# M837-pld-x.net
KiCad netlist of a schematic drawn in EAGLE
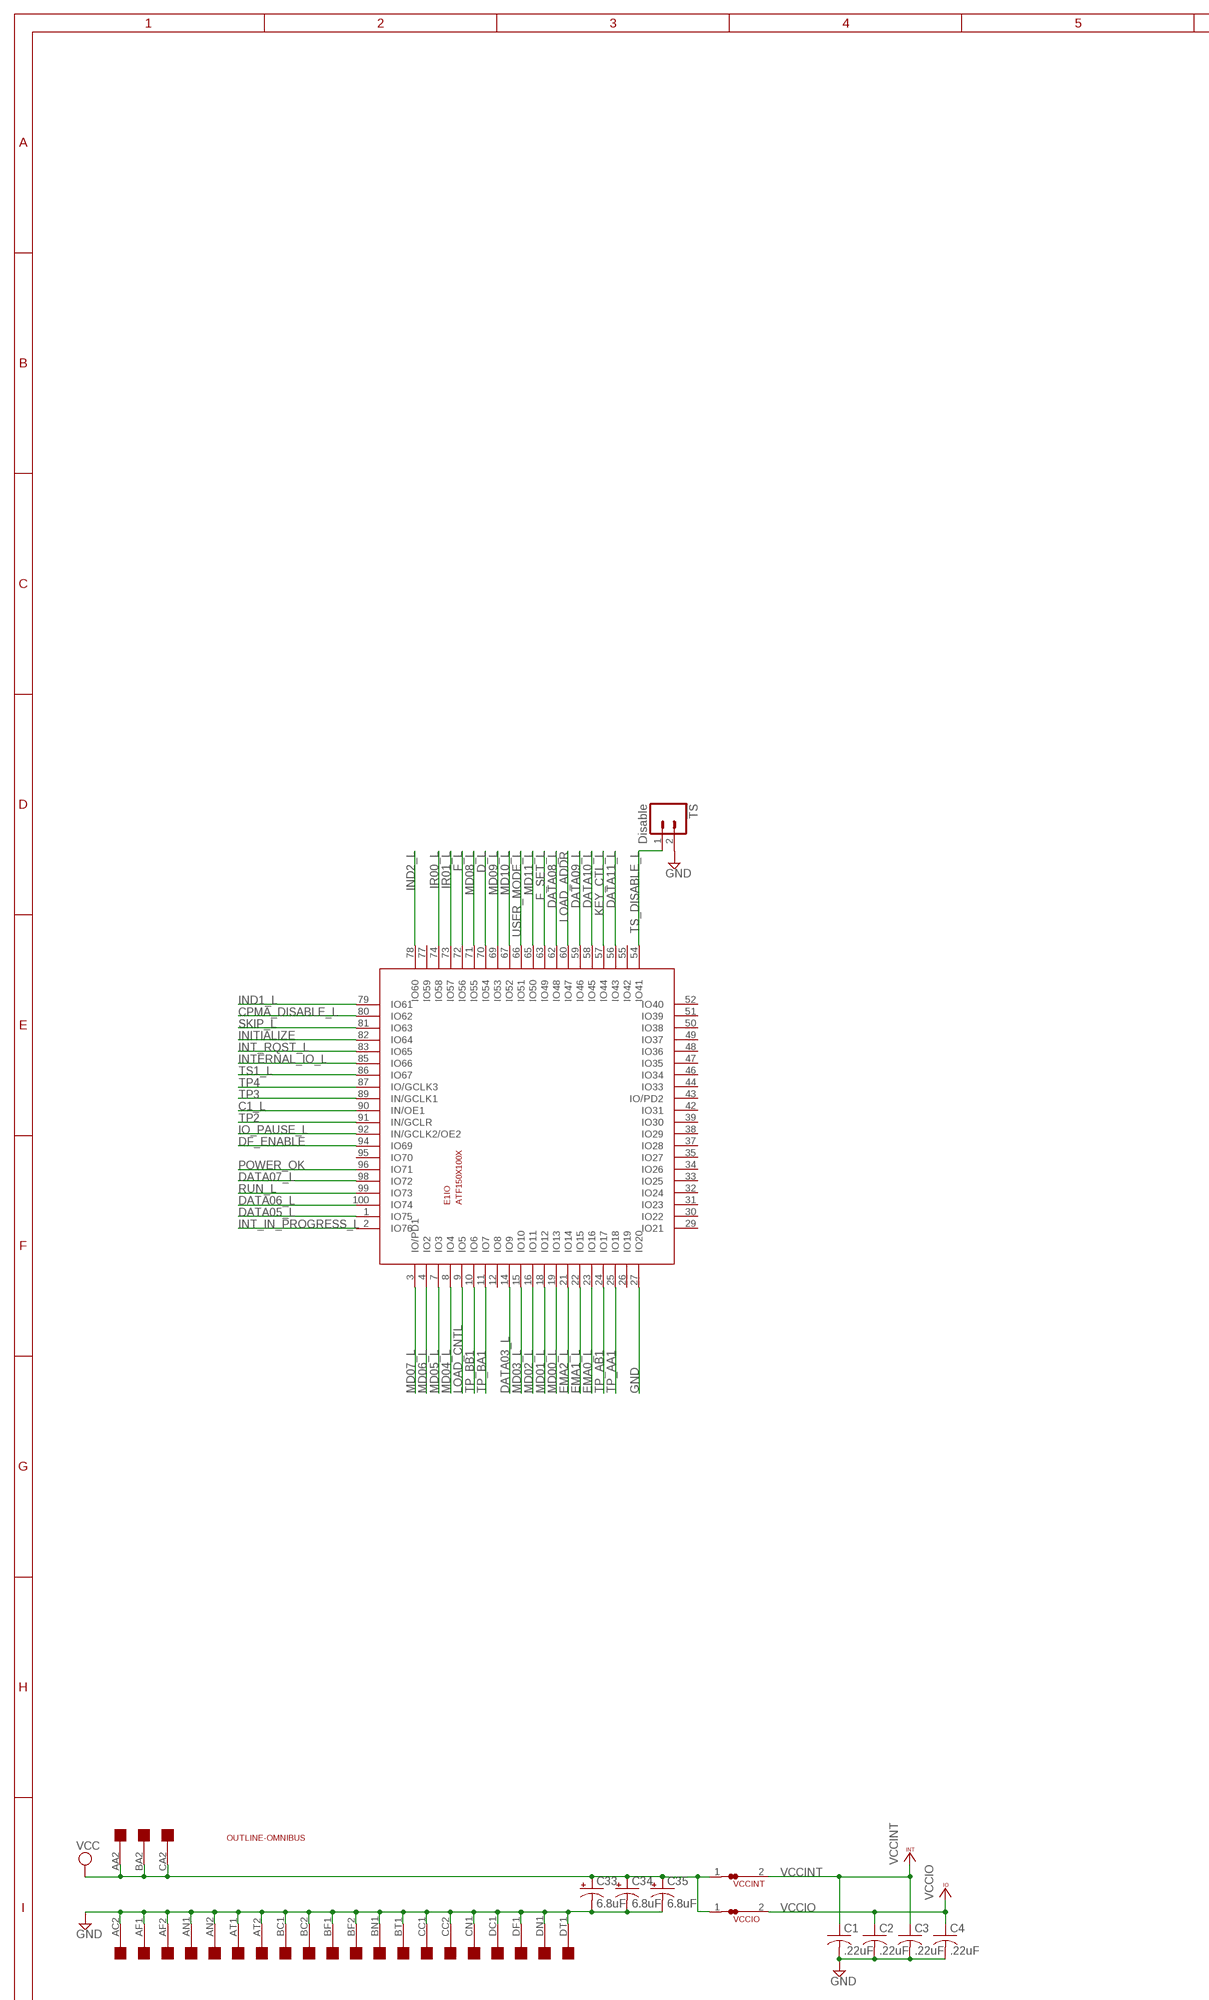
[diagram p0: schematic, sheet 1, part 1 of 2]
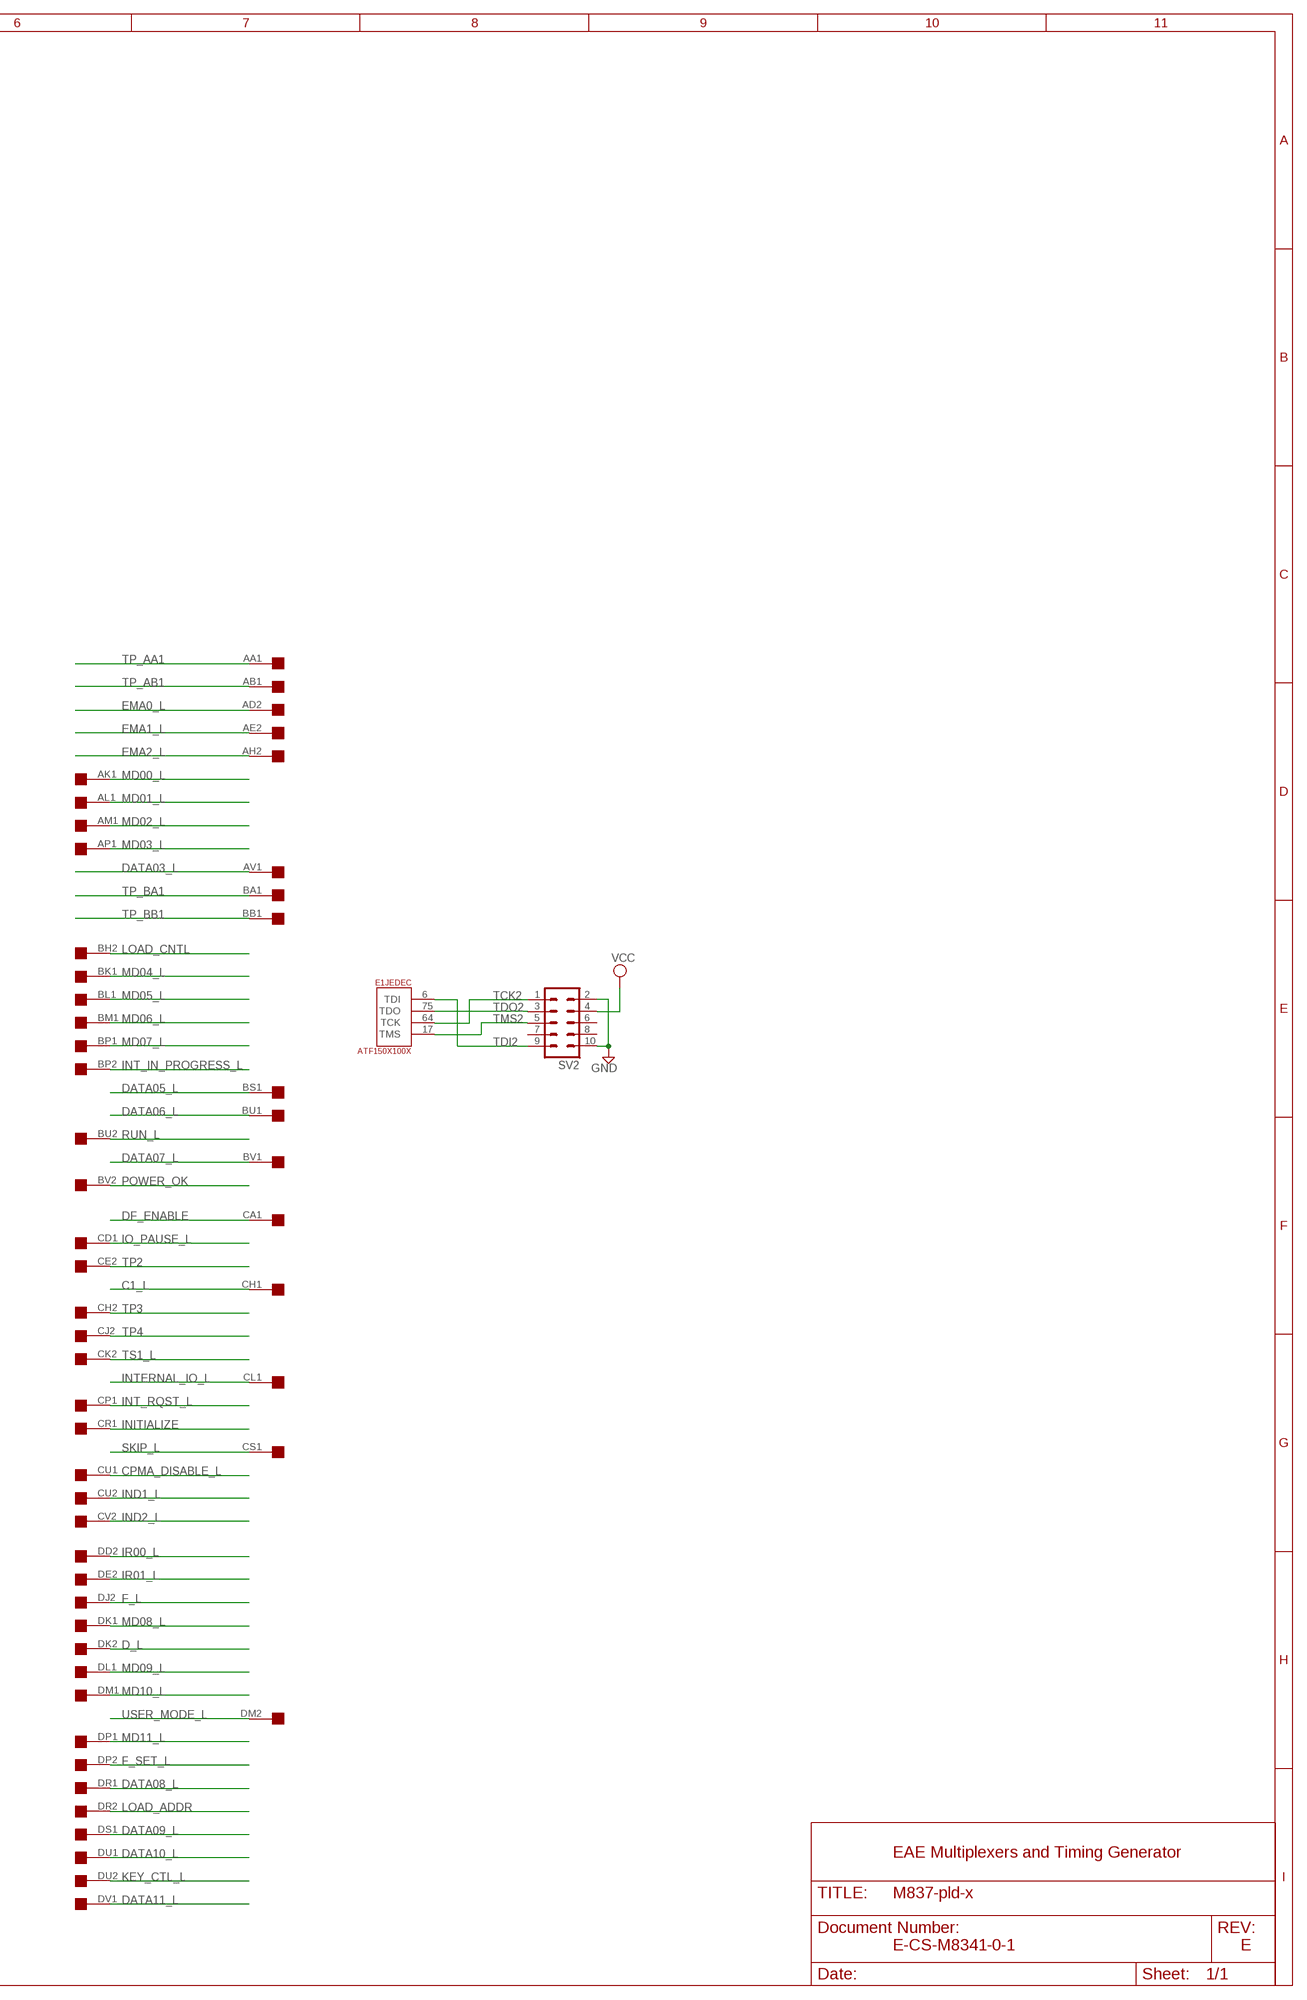
[diagram p1: schematic, sheet 1, part 2 of 2]

(export (version "E")
  (design (tool "Eeschema 10.0.6"))
  (components
    (comp (ref "!TS")
      (value "Disable")
      (footprint "eagle-import:02P")
      (libsource (lib "eagle-import") (part "M02"))
    )
    (comp (ref "C1")
      (value ".22uF")
      (footprint "eagle-import:C063-025X075")
      (libsource (lib "eagle-import") (part "C-US"))
    )
    (comp (ref "C2")
      (value ".22uF")
      (footprint "eagle-import:C063-025X075")
      (libsource (lib "eagle-import") (part "C-US"))
    )
    (comp (ref "C3")
      (value ".22uF")
      (footprint "eagle-import:C063-025X075")
      (libsource (lib "eagle-import") (part "C-US"))
    )
    (comp (ref "C4")
      (value ".22uF")
      (footprint "eagle-import:C063-025X075")
      (libsource (lib "eagle-import") (part "C-US"))
    )
    (comp (ref "C33")
      (value "6.8uF")
      (footprint "eagle-import:E12-8")
      (libsource (lib "eagle-import") (part "CPOL-USE20-8AXIAL"))
    )
    (comp (ref "C34")
      (value "6.8uF")
      (footprint "eagle-import:E12-8")
      (libsource (lib "eagle-import") (part "CPOL-USE20-8AXIAL"))
    )
    (comp (ref "C35")
      (value "6.8uF")
      (footprint "eagle-import:E12-8")
      (libsource (lib "eagle-import") (part "CPOL-USE20-8AXIAL"))
    )
    (comp (ref "E1")
      (value "ATF150X100X")
      (footprint "eagle-import:TH100B")
      (libsource (lib "eagle-import") (part "ATF150X100X"))
    )
    (comp (ref "SV2")
      (value "ML10")
      (footprint "eagle-import:ML10")
      (libsource (lib "eagle-import") (part "ML10"))
    )
    (comp (ref "U$1")
      (value "QUAD")
      (footprint "eagle-import:EDGE-CON8")
      (libsource (lib "eagle-import") (part "QUAD"))
    )
    (comp (ref "U$2")
      (value "OUTLINE-OMNIBUS")
      (footprint "eagle-import:OMNIBUS")
      (libsource (lib "eagle-import") (part "OUTLINE-OMNIBUS"))
    )
    (comp (ref "VCCINT")
      (value "JUMPER-NC1")
      (footprint "eagle-import:NC1")
      (libsource (lib "eagle-import") (part "JUMPER-NC1"))
    )
    (comp (ref "VCCIO")
      (value "JUMPER-NC1")
      (footprint "eagle-import:NC1")
      (libsource (lib "eagle-import") (part "JUMPER-NC1"))
    )
  )
  (nets
    (net (code "1") (name "/C1_L") (class "Default")
      (node (ref "E1") (pin "90") (pinfunction "IN/OE1_90") (pintype "input"))
      (node (ref "U$1") (pin "CH1") (pinfunction "1_CH1") (pintype "bidirectional"))
    )
    (net (code "2") (name "/CPMA_DISABLE_L") (class "Default")
      (node (ref "E1") (pin "80") (pinfunction "IO62_80") (pintype "bidirectional"))
      (node (ref "U$1") (pin "CU1") (pinfunction "1_CU1") (pintype "bidirectional"))
    )
    (net (code "3") (name "/DATA03_L") (class "Default")
      (node (ref "E1") (pin "14") (pinfunction "IO9_14") (pintype "bidirectional"))
      (node (ref "U$1") (pin "AV1") (pinfunction "1_AV1") (pintype "bidirectional"))
    )
    (net (code "4") (name "/DATA05_L") (class "Default")
      (node (ref "E1") (pin "1") (pinfunction "IO75_1") (pintype "bidirectional"))
      (node (ref "U$1") (pin "BS1") (pinfunction "1_BS1") (pintype "bidirectional"))
    )
    (net (code "5") (name "/DATA06_L") (class "Default")
      (node (ref "E1") (pin "100") (pinfunction "IO74_100") (pintype "bidirectional"))
      (node (ref "U$1") (pin "BU1") (pinfunction "1_BU1") (pintype "bidirectional"))
    )
    (net (code "6") (name "/DATA07_L") (class "Default")
      (node (ref "E1") (pin "98") (pinfunction "IO72_98") (pintype "bidirectional"))
      (node (ref "U$1") (pin "BV1") (pinfunction "1_BV1") (pintype "bidirectional"))
    )
    (net (code "7") (name "/DATA08_L") (class "Default")
      (node (ref "E1") (pin "62") (pinfunction "IO48_62") (pintype "bidirectional"))
      (node (ref "U$1") (pin "DR1") (pinfunction "1_DR1") (pintype "bidirectional"))
    )
    (net (code "8") (name "/DATA09_L") (class "Default")
      (node (ref "E1") (pin "59") (pinfunction "IO46_59") (pintype "bidirectional"))
      (node (ref "U$1") (pin "DS1") (pinfunction "1_DS1") (pintype "bidirectional"))
    )
    (net (code "9") (name "/DATA10_L") (class "Default")
      (node (ref "E1") (pin "58") (pinfunction "IO45_58") (pintype "bidirectional"))
      (node (ref "U$1") (pin "DU1") (pinfunction "1_DU1") (pintype "bidirectional"))
    )
    (net (code "10") (name "/DATA11_L") (class "Default")
      (node (ref "E1") (pin "56") (pinfunction "IO43_56") (pintype "bidirectional"))
      (node (ref "U$1") (pin "DV1") (pinfunction "1_DV1") (pintype "bidirectional"))
    )
    (net (code "11") (name "/DF_ENABLE") (class "Default")
      (node (ref "E1") (pin "94") (pinfunction "IO69_94") (pintype "bidirectional"))
      (node (ref "U$1") (pin "CA1") (pinfunction "1_CA1") (pintype "bidirectional"))
    )
    (net (code "12") (name "/D_L") (class "Default")
      (node (ref "E1") (pin "70") (pinfunction "IO54_70") (pintype "bidirectional"))
      (node (ref "U$1") (pin "DK2") (pinfunction "1_DK2") (pintype "bidirectional"))
    )
    (net (code "13") (name "/EMA0_L") (class "Default")
      (node (ref "E1") (pin "23") (pinfunction "IO16_23") (pintype "bidirectional"))
      (node (ref "U$1") (pin "AD2") (pinfunction "1_AD2") (pintype "bidirectional"))
    )
    (net (code "14") (name "/EMA1_L") (class "Default")
      (node (ref "E1") (pin "22") (pinfunction "IO15_22") (pintype "bidirectional"))
      (node (ref "U$1") (pin "AE2") (pinfunction "1_AE2") (pintype "bidirectional"))
    )
    (net (code "15") (name "/EMA2_L") (class "Default")
      (node (ref "E1") (pin "21") (pinfunction "IO14_21") (pintype "bidirectional"))
      (node (ref "U$1") (pin "AH2") (pinfunction "1_AH2") (pintype "bidirectional"))
    )
    (net (code "16") (name "/F_L") (class "Default")
      (node (ref "E1") (pin "72") (pinfunction "IO56_72") (pintype "bidirectional"))
      (node (ref "U$1") (pin "DJ2") (pinfunction "1_DJ2") (pintype "bidirectional"))
    )
    (net (code "17") (name "/F_SET_L") (class "Default")
      (node (ref "E1") (pin "63") (pinfunction "IO49_63") (pintype "bidirectional"))
      (node (ref "U$1") (pin "DP2") (pinfunction "1_DP2") (pintype "bidirectional"))
    )
    (net (code "18") (name "/IND1_L") (class "Default")
      (node (ref "E1") (pin "79") (pinfunction "IO61_79") (pintype "bidirectional"))
      (node (ref "U$1") (pin "CU2") (pinfunction "1_CU2") (pintype "bidirectional"))
    )
    (net (code "19") (name "/IND2_L") (class "Default")
      (node (ref "E1") (pin "78") (pinfunction "IO60_78") (pintype "bidirectional"))
      (node (ref "U$1") (pin "CV2") (pinfunction "1_CV2") (pintype "bidirectional"))
    )
    (net (code "20") (name "/INITIALIZE") (class "Default")
      (node (ref "E1") (pin "82") (pinfunction "IO64_82") (pintype "bidirectional"))
      (node (ref "U$1") (pin "CR1") (pinfunction "1_CR1") (pintype "bidirectional"))
    )
    (net (code "21") (name "/INTERNAL_IO_L") (class "Default")
      (node (ref "E1") (pin "85") (pinfunction "IO66_85") (pintype "bidirectional"))
      (node (ref "U$1") (pin "CL1") (pinfunction "1_CL1") (pintype "bidirectional"))
    )
    (net (code "22") (name "/INT_IN_PROGRESS_L") (class "Default")
      (node (ref "E1") (pin "2") (pinfunction "IO76_2") (pintype "bidirectional"))
      (node (ref "U$1") (pin "BP2") (pinfunction "1_BP2") (pintype "bidirectional"))
    )
    (net (code "23") (name "/INT_RQST_L") (class "Default")
      (node (ref "E1") (pin "83") (pinfunction "IO65_83") (pintype "bidirectional"))
      (node (ref "U$1") (pin "CP1") (pinfunction "1_CP1") (pintype "bidirectional"))
    )
    (net (code "24") (name "/IO_PAUSE_L") (class "Default")
      (node (ref "E1") (pin "92") (pinfunction "IN/GCLK2/OE2_92") (pintype "input"))
      (node (ref "U$1") (pin "CD1") (pinfunction "1_CD1") (pintype "bidirectional"))
    )
    (net (code "25") (name "/IR00_L") (class "Default")
      (node (ref "E1") (pin "74") (pinfunction "IO58_74") (pintype "bidirectional"))
      (node (ref "U$1") (pin "DD2") (pinfunction "1_DD2") (pintype "bidirectional"))
    )
    (net (code "26") (name "/IR01_L") (class "Default")
      (node (ref "E1") (pin "73") (pinfunction "IO57_73") (pintype "bidirectional"))
      (node (ref "U$1") (pin "DE2") (pinfunction "1_DE2") (pintype "bidirectional"))
    )
    (net (code "27") (name "/KEY_CTL_L") (class "Default")
      (node (ref "E1") (pin "57") (pinfunction "IO44_57") (pintype "bidirectional"))
      (node (ref "U$1") (pin "DU2") (pinfunction "1_DU2") (pintype "bidirectional"))
    )
    (net (code "28") (name "/LOAD_ADDR") (class "Default")
      (node (ref "E1") (pin "60") (pinfunction "IO47_60") (pintype "bidirectional"))
      (node (ref "U$1") (pin "DR2") (pinfunction "1_DR2") (pintype "bidirectional"))
    )
    (net (code "29") (name "/LOAD_CNTL") (class "Default")
      (node (ref "E1") (pin "9") (pinfunction "IO5_9") (pintype "bidirectional"))
      (node (ref "U$1") (pin "BH2") (pinfunction "1_BH2") (pintype "bidirectional"))
    )
    (net (code "30") (name "/MD00_L") (class "Default")
      (node (ref "E1") (pin "19") (pinfunction "IO13_19") (pintype "bidirectional"))
      (node (ref "U$1") (pin "AK1") (pinfunction "1_AK1") (pintype "bidirectional"))
    )
    (net (code "31") (name "/MD01_L") (class "Default")
      (node (ref "E1") (pin "18") (pinfunction "IO12_18") (pintype "bidirectional"))
      (node (ref "U$1") (pin "AL1") (pinfunction "1_AL1") (pintype "bidirectional"))
    )
    (net (code "32") (name "/MD02_L") (class "Default")
      (node (ref "E1") (pin "16") (pinfunction "IO11_16") (pintype "bidirectional"))
      (node (ref "U$1") (pin "AM1") (pinfunction "1_AM1") (pintype "bidirectional"))
    )
    (net (code "33") (name "/MD03_L") (class "Default")
      (node (ref "E1") (pin "15") (pinfunction "IO10_15") (pintype "bidirectional"))
      (node (ref "U$1") (pin "AP1") (pinfunction "1_AP1") (pintype "bidirectional"))
    )
    (net (code "34") (name "/MD04_L") (class "Default")
      (node (ref "E1") (pin "8") (pinfunction "IO4_8") (pintype "bidirectional"))
      (node (ref "U$1") (pin "BK1") (pinfunction "1_BK1") (pintype "bidirectional"))
    )
    (net (code "35") (name "/MD05_L") (class "Default")
      (node (ref "E1") (pin "7") (pinfunction "IO3_7") (pintype "bidirectional"))
      (node (ref "U$1") (pin "BL1") (pinfunction "1_BL1") (pintype "bidirectional"))
    )
    (net (code "36") (name "/MD06_L") (class "Default")
      (node (ref "E1") (pin "4") (pinfunction "IO2_4") (pintype "bidirectional"))
      (node (ref "U$1") (pin "BM1") (pinfunction "1_BM1") (pintype "bidirectional"))
    )
    (net (code "37") (name "/MD07_L") (class "Default")
      (node (ref "E1") (pin "3") (pinfunction "IO/PD1_3") (pintype "bidirectional"))
      (node (ref "U$1") (pin "BP1") (pinfunction "1_BP1") (pintype "bidirectional"))
    )
    (net (code "38") (name "/MD08_L") (class "Default")
      (node (ref "E1") (pin "71") (pinfunction "IO55_71") (pintype "bidirectional"))
      (node (ref "U$1") (pin "DK1") (pinfunction "1_DK1") (pintype "bidirectional"))
    )
    (net (code "39") (name "/MD09_L") (class "Default")
      (node (ref "E1") (pin "69") (pinfunction "IO53_69") (pintype "bidirectional"))
      (node (ref "U$1") (pin "DL1") (pinfunction "1_DL1") (pintype "bidirectional"))
    )
    (net (code "40") (name "/MD10_L") (class "Default")
      (node (ref "E1") (pin "67") (pinfunction "IO52_67") (pintype "bidirectional"))
      (node (ref "U$1") (pin "DM1") (pinfunction "1_DM1") (pintype "bidirectional"))
    )
    (net (code "41") (name "/MD11_L") (class "Default")
      (node (ref "E1") (pin "65") (pinfunction "IO50_65") (pintype "bidirectional"))
      (node (ref "U$1") (pin "DP1") (pinfunction "1_DP1") (pintype "bidirectional"))
    )
    (net (code "42") (name "/POWER_OK") (class "Default")
      (node (ref "E1") (pin "96") (pinfunction "IO71_96") (pintype "bidirectional"))
      (node (ref "U$1") (pin "BV2") (pinfunction "1_BV2") (pintype "bidirectional"))
    )
    (net (code "43") (name "/RUN_L") (class "Default")
      (node (ref "E1") (pin "99") (pinfunction "IO73_99") (pintype "bidirectional"))
      (node (ref "U$1") (pin "BU2") (pinfunction "1_BU2") (pintype "bidirectional"))
    )
    (net (code "44") (name "/SKIP_L") (class "Default")
      (node (ref "E1") (pin "81") (pinfunction "IO63_81") (pintype "bidirectional"))
      (node (ref "U$1") (pin "CS1") (pinfunction "1_CS1") (pintype "bidirectional"))
    )
    (net (code "45") (name "/TCK2") (class "Default")
      (node (ref "E1") (pin "64") (pinfunction "TCK_64") (pintype "bidirectional"))
      (node (ref "SV2") (pin "1") (pinfunction "1_1") (pintype "passive"))
    )
    (net (code "46") (name "/TDI2") (class "Default")
      (node (ref "E1") (pin "6") (pinfunction "TDI_6") (pintype "bidirectional"))
      (node (ref "SV2") (pin "9") (pinfunction "9_9") (pintype "passive"))
    )
    (net (code "47") (name "/TDO2") (class "Default")
      (node (ref "E1") (pin "75") (pinfunction "TDO_75") (pintype "bidirectional"))
      (node (ref "SV2") (pin "3") (pinfunction "3_3") (pintype "passive"))
    )
    (net (code "48") (name "/TMS2") (class "Default")
      (node (ref "E1") (pin "17") (pinfunction "TMS_17") (pintype "bidirectional"))
      (node (ref "SV2") (pin "5") (pinfunction "5_5") (pintype "passive"))
    )
    (net (code "49") (name "/TP2") (class "Default")
      (node (ref "E1") (pin "91") (pinfunction "IN/GCLR_91") (pintype "input"))
      (node (ref "U$1") (pin "CE2") (pinfunction "1_CE2") (pintype "bidirectional"))
    )
    (net (code "50") (name "/TP3") (class "Default")
      (node (ref "E1") (pin "89") (pinfunction "IN/GCLK1_89") (pintype "input"))
      (node (ref "U$1") (pin "CH2") (pinfunction "1_CH2") (pintype "bidirectional"))
    )
    (net (code "51") (name "/TP4") (class "Default")
      (node (ref "E1") (pin "87") (pinfunction "IO/GCLK3_87") (pintype "bidirectional"))
      (node (ref "U$1") (pin "CJ2") (pinfunction "1_CJ2") (pintype "bidirectional"))
    )
    (net (code "52") (name "/TP_AA1") (class "Default")
      (node (ref "E1") (pin "25") (pinfunction "IO18_25") (pintype "bidirectional"))
      (node (ref "U$1") (pin "AA1") (pinfunction "1_AA1") (pintype "bidirectional"))
    )
    (net (code "53") (name "/TP_AB1") (class "Default")
      (node (ref "E1") (pin "24") (pinfunction "IO17_24") (pintype "bidirectional"))
      (node (ref "U$1") (pin "AB1") (pinfunction "1_AB1") (pintype "bidirectional"))
    )
    (net (code "54") (name "/TP_BA1") (class "Default")
      (node (ref "E1") (pin "11") (pinfunction "IO7_11") (pintype "bidirectional"))
      (node (ref "U$1") (pin "BA1") (pinfunction "1_BA1") (pintype "bidirectional"))
    )
    (net (code "55") (name "/TP_BB1") (class "Default")
      (node (ref "E1") (pin "10") (pinfunction "IO6_10") (pintype "bidirectional"))
      (node (ref "U$1") (pin "BB1") (pinfunction "1_BB1") (pintype "bidirectional"))
    )
    (net (code "56") (name "/TS1_L") (class "Default")
      (node (ref "E1") (pin "86") (pinfunction "IO67_86") (pintype "bidirectional"))
      (node (ref "U$1") (pin "CK2") (pinfunction "1_CK2") (pintype "bidirectional"))
    )
    (net (code "57") (name "/TS_DISABLE_L") (class "Default")
      (node (ref "!TS") (pin "1") (pinfunction "1_1") (pintype "passive"))
      (node (ref "E1") (pin "54") (pinfunction "IO41_54") (pintype "bidirectional"))
    )
    (net (code "58") (name "/USER_MODE_L") (class "Default")
      (node (ref "E1") (pin "66") (pinfunction "IO51_66") (pintype "bidirectional"))
      (node (ref "U$1") (pin "DM2") (pinfunction "1_DM2") (pintype "bidirectional"))
    )
    (net (code "59") (name "GND") (class "Default")
      (node (ref "!TS") (pin "2") (pinfunction "2_2") (pintype "passive"))
      (node (ref "C1") (pin "2") (pinfunction "2_2") (pintype "passive"))
      (node (ref "C2") (pin "2") (pinfunction "2_2") (pintype "passive"))
      (node (ref "C3") (pin "2") (pinfunction "2_2") (pintype "passive"))
      (node (ref "C33") (pin "-") (pinfunction "-_-") (pintype "passive"))
      (node (ref "C34") (pin "-") (pinfunction "-_-") (pintype "passive"))
      (node (ref "C35") (pin "-") (pinfunction "-_-") (pintype "passive"))
      (node (ref "C4") (pin "2") (pinfunction "2_2") (pintype "passive"))
      (node (ref "E1") (pin "27") (pinfunction "IO20_27") (pintype "bidirectional"))
      (node (ref "SV2") (pin "10") (pinfunction "10_10") (pintype "passive"))
      (node (ref "SV2") (pin "2") (pinfunction "2_2") (pintype "passive"))
      (node (ref "U$1") (pin "AC2") (pinfunction "1_AC2") (pintype "bidirectional"))
      (node (ref "U$1") (pin "AF1") (pinfunction "1_AF1") (pintype "bidirectional"))
      (node (ref "U$1") (pin "AF2") (pinfunction "1_AF2") (pintype "bidirectional"))
      (node (ref "U$1") (pin "AN1") (pinfunction "1_AN1") (pintype "bidirectional"))
      (node (ref "U$1") (pin "AN2") (pinfunction "1_AN2") (pintype "bidirectional"))
      (node (ref "U$1") (pin "AT1") (pinfunction "1_AT1") (pintype "bidirectional"))
      (node (ref "U$1") (pin "AT2") (pinfunction "1_AT2") (pintype "bidirectional"))
      (node (ref "U$1") (pin "BC1") (pinfunction "1_BC1") (pintype "bidirectional"))
      (node (ref "U$1") (pin "BC2") (pinfunction "1_BC2") (pintype "bidirectional"))
      (node (ref "U$1") (pin "BF1") (pinfunction "1_BF1") (pintype "bidirectional"))
      (node (ref "U$1") (pin "BF2") (pinfunction "1_BF2") (pintype "bidirectional"))
      (node (ref "U$1") (pin "BN1") (pinfunction "1_BN1") (pintype "bidirectional"))
      (node (ref "U$1") (pin "BT1") (pinfunction "1_BT1") (pintype "bidirectional"))
      (node (ref "U$1") (pin "CC1") (pinfunction "1_CC1") (pintype "bidirectional"))
      (node (ref "U$1") (pin "CC2") (pinfunction "1_CC2") (pintype "bidirectional"))
      (node (ref "U$1") (pin "CN1") (pinfunction "1_CN1") (pintype "bidirectional"))
      (node (ref "U$1") (pin "DC1") (pinfunction "1_DC1") (pintype "bidirectional"))
      (node (ref "U$1") (pin "DF1") (pinfunction "1_DF1") (pintype "bidirectional"))
      (node (ref "U$1") (pin "DN1") (pinfunction "1_DN1") (pintype "bidirectional"))
      (node (ref "U$1") (pin "DT1") (pinfunction "1_DT1") (pintype "bidirectional"))
    )
    (net (code "60") (name "VCC") (class "Default")
      (node (ref "C33") (pin "+") (pinfunction "+_+") (pintype "passive"))
      (node (ref "C34") (pin "+") (pinfunction "+_+") (pintype "passive"))
      (node (ref "C35") (pin "+") (pinfunction "+_+") (pintype "passive"))
      (node (ref "SV2") (pin "4") (pinfunction "4_4") (pintype "passive"))
      (node (ref "U$1") (pin "AA2") (pinfunction "1_AA2") (pintype "bidirectional"))
      (node (ref "U$1") (pin "BA2") (pinfunction "1_BA2") (pintype "bidirectional"))
      (node (ref "U$1") (pin "CA2") (pinfunction "1_CA2") (pintype "bidirectional"))
      (node (ref "VCCINT") (pin "1") (pinfunction "1_1") (pintype "bidirectional"))
      (node (ref "VCCIO") (pin "1") (pinfunction "1_1") (pintype "bidirectional"))
    )
    (net (code "61") (name "VCCINT") (class "Default")
      (node (ref "C1") (pin "1") (pinfunction "1_1") (pintype "passive"))
      (node (ref "C3") (pin "1") (pinfunction "1_1") (pintype "passive"))
      (node (ref "VCCINT") (pin "2") (pinfunction "2_2") (pintype "bidirectional"))
    )
    (net (code "62") (name "VCCIO") (class "Default")
      (node (ref "C2") (pin "1") (pinfunction "1_1") (pintype "passive"))
      (node (ref "C4") (pin "1") (pinfunction "1_1") (pintype "passive"))
      (node (ref "VCCIO") (pin "2") (pinfunction "2_2") (pintype "bidirectional"))
    )
    (net (code "63") (name "unconnected-(E1Q-IO8-Pad12)") (class "Default")
      (node (ref "E1") (pin "12") (pinfunction "IO8_12") (pintype "bidirectional"))
    )
    (net (code "64") (name "unconnected-(E1Q-IO19-Pad26)") (class "Default")
      (node (ref "E1") (pin "26") (pinfunction "IO19_26") (pintype "bidirectional"))
    )
    (net (code "65") (name "unconnected-(E1Q-IO21-Pad29)") (class "Default")
      (node (ref "E1") (pin "29") (pinfunction "IO21_29") (pintype "bidirectional"))
    )
    (net (code "66") (name "unconnected-(E1Q-IO22-Pad30)") (class "Default")
      (node (ref "E1") (pin "30") (pinfunction "IO22_30") (pintype "bidirectional"))
    )
    (net (code "67") (name "unconnected-(E1Q-IO23-Pad31)") (class "Default")
      (node (ref "E1") (pin "31") (pinfunction "IO23_31") (pintype "bidirectional"))
    )
    (net (code "68") (name "unconnected-(E1Q-IO24-Pad32)") (class "Default")
      (node (ref "E1") (pin "32") (pinfunction "IO24_32") (pintype "bidirectional"))
    )
    (net (code "69") (name "unconnected-(E1Q-IO25-Pad33)") (class "Default")
      (node (ref "E1") (pin "33") (pinfunction "IO25_33") (pintype "bidirectional"))
    )
    (net (code "70") (name "unconnected-(E1Q-IO26-Pad34)") (class "Default")
      (node (ref "E1") (pin "34") (pinfunction "IO26_34") (pintype "bidirectional"))
    )
    (net (code "71") (name "unconnected-(E1Q-IO27-Pad35)") (class "Default")
      (node (ref "E1") (pin "35") (pinfunction "IO27_35") (pintype "bidirectional"))
    )
    (net (code "72") (name "unconnected-(E1Q-IO28-Pad37)") (class "Default")
      (node (ref "E1") (pin "37") (pinfunction "IO28_37") (pintype "bidirectional"))
    )
    (net (code "73") (name "unconnected-(E1Q-IO29-Pad38)") (class "Default")
      (node (ref "E1") (pin "38") (pinfunction "IO29_38") (pintype "bidirectional"))
    )
    (net (code "74") (name "unconnected-(E1Q-IO30-Pad39)") (class "Default")
      (node (ref "E1") (pin "39") (pinfunction "IO30_39") (pintype "bidirectional"))
    )
    (net (code "75") (name "unconnected-(E1Q-IO31-Pad42)") (class "Default")
      (node (ref "E1") (pin "42") (pinfunction "IO31_42") (pintype "bidirectional"))
    )
    (net (code "76") (name "unconnected-(E1Q-IO33-Pad44)") (class "Default")
      (node (ref "E1") (pin "44") (pinfunction "IO33_44") (pintype "bidirectional"))
    )
    (net (code "77") (name "unconnected-(E1Q-IO34-Pad46)") (class "Default")
      (node (ref "E1") (pin "46") (pinfunction "IO34_46") (pintype "bidirectional"))
    )
    (net (code "78") (name "unconnected-(E1Q-IO35-Pad47)") (class "Default")
      (node (ref "E1") (pin "47") (pinfunction "IO35_47") (pintype "bidirectional"))
    )
    (net (code "79") (name "unconnected-(E1Q-IO36-Pad48)") (class "Default")
      (node (ref "E1") (pin "48") (pinfunction "IO36_48") (pintype "bidirectional"))
    )
    (net (code "80") (name "unconnected-(E1Q-IO37-Pad49)") (class "Default")
      (node (ref "E1") (pin "49") (pinfunction "IO37_49") (pintype "bidirectional"))
    )
    (net (code "81") (name "unconnected-(E1Q-IO38-Pad50)") (class "Default")
      (node (ref "E1") (pin "50") (pinfunction "IO38_50") (pintype "bidirectional"))
    )
    (net (code "82") (name "unconnected-(E1Q-IO39-Pad51)") (class "Default")
      (node (ref "E1") (pin "51") (pinfunction "IO39_51") (pintype "bidirectional"))
    )
    (net (code "83") (name "unconnected-(E1Q-IO40-Pad52)") (class "Default")
      (node (ref "E1") (pin "52") (pinfunction "IO40_52") (pintype "bidirectional"))
    )
    (net (code "84") (name "unconnected-(E1Q-IO42-Pad55)") (class "Default")
      (node (ref "E1") (pin "55") (pinfunction "IO42_55") (pintype "bidirectional"))
    )
    (net (code "85") (name "unconnected-(E1Q-IO59-Pad77)") (class "Default")
      (node (ref "E1") (pin "77") (pinfunction "IO59_77") (pintype "bidirectional"))
    )
    (net (code "86") (name "unconnected-(E1Q-IO70-Pad95)") (class "Default")
      (node (ref "E1") (pin "95") (pinfunction "IO70_95") (pintype "bidirectional"))
    )
    (net (code "87") (name "unconnected-(E1Q-IO{slash}PD2-Pad43)") (class "Default")
      (node (ref "E1") (pin "43") (pinfunction "IO/PD2_43") (pintype "bidirectional"))
    )
    (net (code "88") (name "unconnected-(SV2-Pad6)") (class "Default")
      (node (ref "SV2") (pin "6") (pinfunction "6_6") (pintype "passive"))
    )
    (net (code "89") (name "unconnected-(SV2-Pad7)") (class "Default")
      (node (ref "SV2") (pin "7") (pinfunction "7_7") (pintype "passive"))
    )
    (net (code "90") (name "unconnected-(SV2-Pad8)") (class "Default")
      (node (ref "SV2") (pin "8") (pinfunction "8_8") (pintype "passive"))
    )
  )
)
